# adapter-50-100mil-x12.net
KiCad netlist of a schematic drawn in Altium Designer
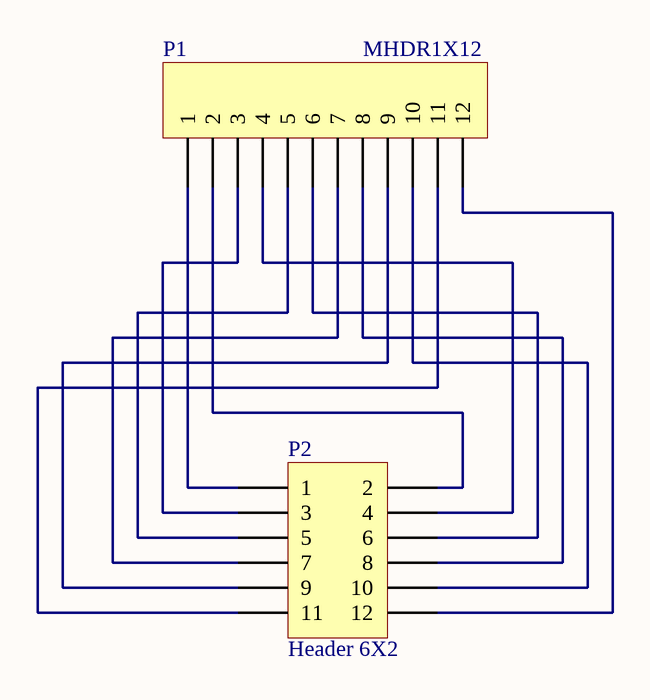
[diagram p0: adapter-50-100mil-x12.SchDoc]

(export (version "E")
  (design (tool "Eeschema 10.0.6"))
  (components
    (comp (ref "P1")
      (value "MHDR1X12")
      (footprint "MHDR1X12")
      (description "Header, 12-Pin")
      (fields (field (name "PUBLISHER") "Altium Limited"))
      (libsource (lib "Miscellaneous Connectors") (part "MHDR1X12"))
    )
    (comp (ref "P2")
      (value "Header 6X2")
      (footprint "HDR2X6")
      (description "Header, 6-Pin, Dual row")
      (fields (field (name "PUBLISHER") "Altium Limited"))
      (libsource (lib "Miscellaneous Connectors") (part "Header 6X2"))
    )
  )
  (nets
    (net (code "1") (name "Net-(P1-Pad1)") (class "Default")
      (node (ref "P1") (pin "1") (pinfunction "1_1") (pintype "passive"))
      (node (ref "P2") (pin "1") (pinfunction "1_1") (pintype "passive"))
    )
    (net (code "2") (name "Net-(P1-Pad2)") (class "Default")
      (node (ref "P1") (pin "2") (pinfunction "2_2") (pintype "passive"))
      (node (ref "P2") (pin "2") (pinfunction "2_2") (pintype "passive"))
    )
    (net (code "3") (name "Net-(P1-Pad3)") (class "Default")
      (node (ref "P1") (pin "3") (pinfunction "3_3") (pintype "passive"))
      (node (ref "P2") (pin "3") (pinfunction "3_3") (pintype "passive"))
    )
    (net (code "4") (name "Net-(P1-Pad4)") (class "Default")
      (node (ref "P1") (pin "4") (pinfunction "4_4") (pintype "passive"))
      (node (ref "P2") (pin "4") (pinfunction "4_4") (pintype "passive"))
    )
    (net (code "5") (name "Net-(P1-Pad5)") (class "Default")
      (node (ref "P1") (pin "5") (pinfunction "5_5") (pintype "passive"))
      (node (ref "P2") (pin "5") (pinfunction "5_5") (pintype "passive"))
    )
    (net (code "6") (name "Net-(P1-Pad6)") (class "Default")
      (node (ref "P1") (pin "6") (pinfunction "6_6") (pintype "passive"))
      (node (ref "P2") (pin "6") (pinfunction "6_6") (pintype "passive"))
    )
    (net (code "7") (name "Net-(P1-Pad7)") (class "Default")
      (node (ref "P1") (pin "7") (pinfunction "7_7") (pintype "passive"))
      (node (ref "P2") (pin "7") (pinfunction "7_7") (pintype "passive"))
    )
    (net (code "8") (name "Net-(P1-Pad8)") (class "Default")
      (node (ref "P1") (pin "8") (pinfunction "8_8") (pintype "passive"))
      (node (ref "P2") (pin "8") (pinfunction "8_8") (pintype "passive"))
    )
    (net (code "9") (name "Net-(P1-Pad9)") (class "Default")
      (node (ref "P1") (pin "9") (pinfunction "9_9") (pintype "passive"))
      (node (ref "P2") (pin "9") (pinfunction "9_9") (pintype "passive"))
    )
    (net (code "10") (name "Net-(P1-Pad10)") (class "Default")
      (node (ref "P1") (pin "10") (pinfunction "10_10") (pintype "passive"))
      (node (ref "P2") (pin "10") (pinfunction "10_10") (pintype "passive"))
    )
    (net (code "11") (name "Net-(P1-Pad11)") (class "Default")
      (node (ref "P1") (pin "11") (pinfunction "11_11") (pintype "passive"))
      (node (ref "P2") (pin "11") (pinfunction "11_11") (pintype "passive"))
    )
    (net (code "12") (name "Net-(P1-Pad12)") (class "Default")
      (node (ref "P1") (pin "12") (pinfunction "12_12") (pintype "passive"))
      (node (ref "P2") (pin "12") (pinfunction "12_12") (pintype "passive"))
    )
  )
)
